# Booster_scheme_transformator.net
KiCad netlist of a schematic drawn in Altium Designer
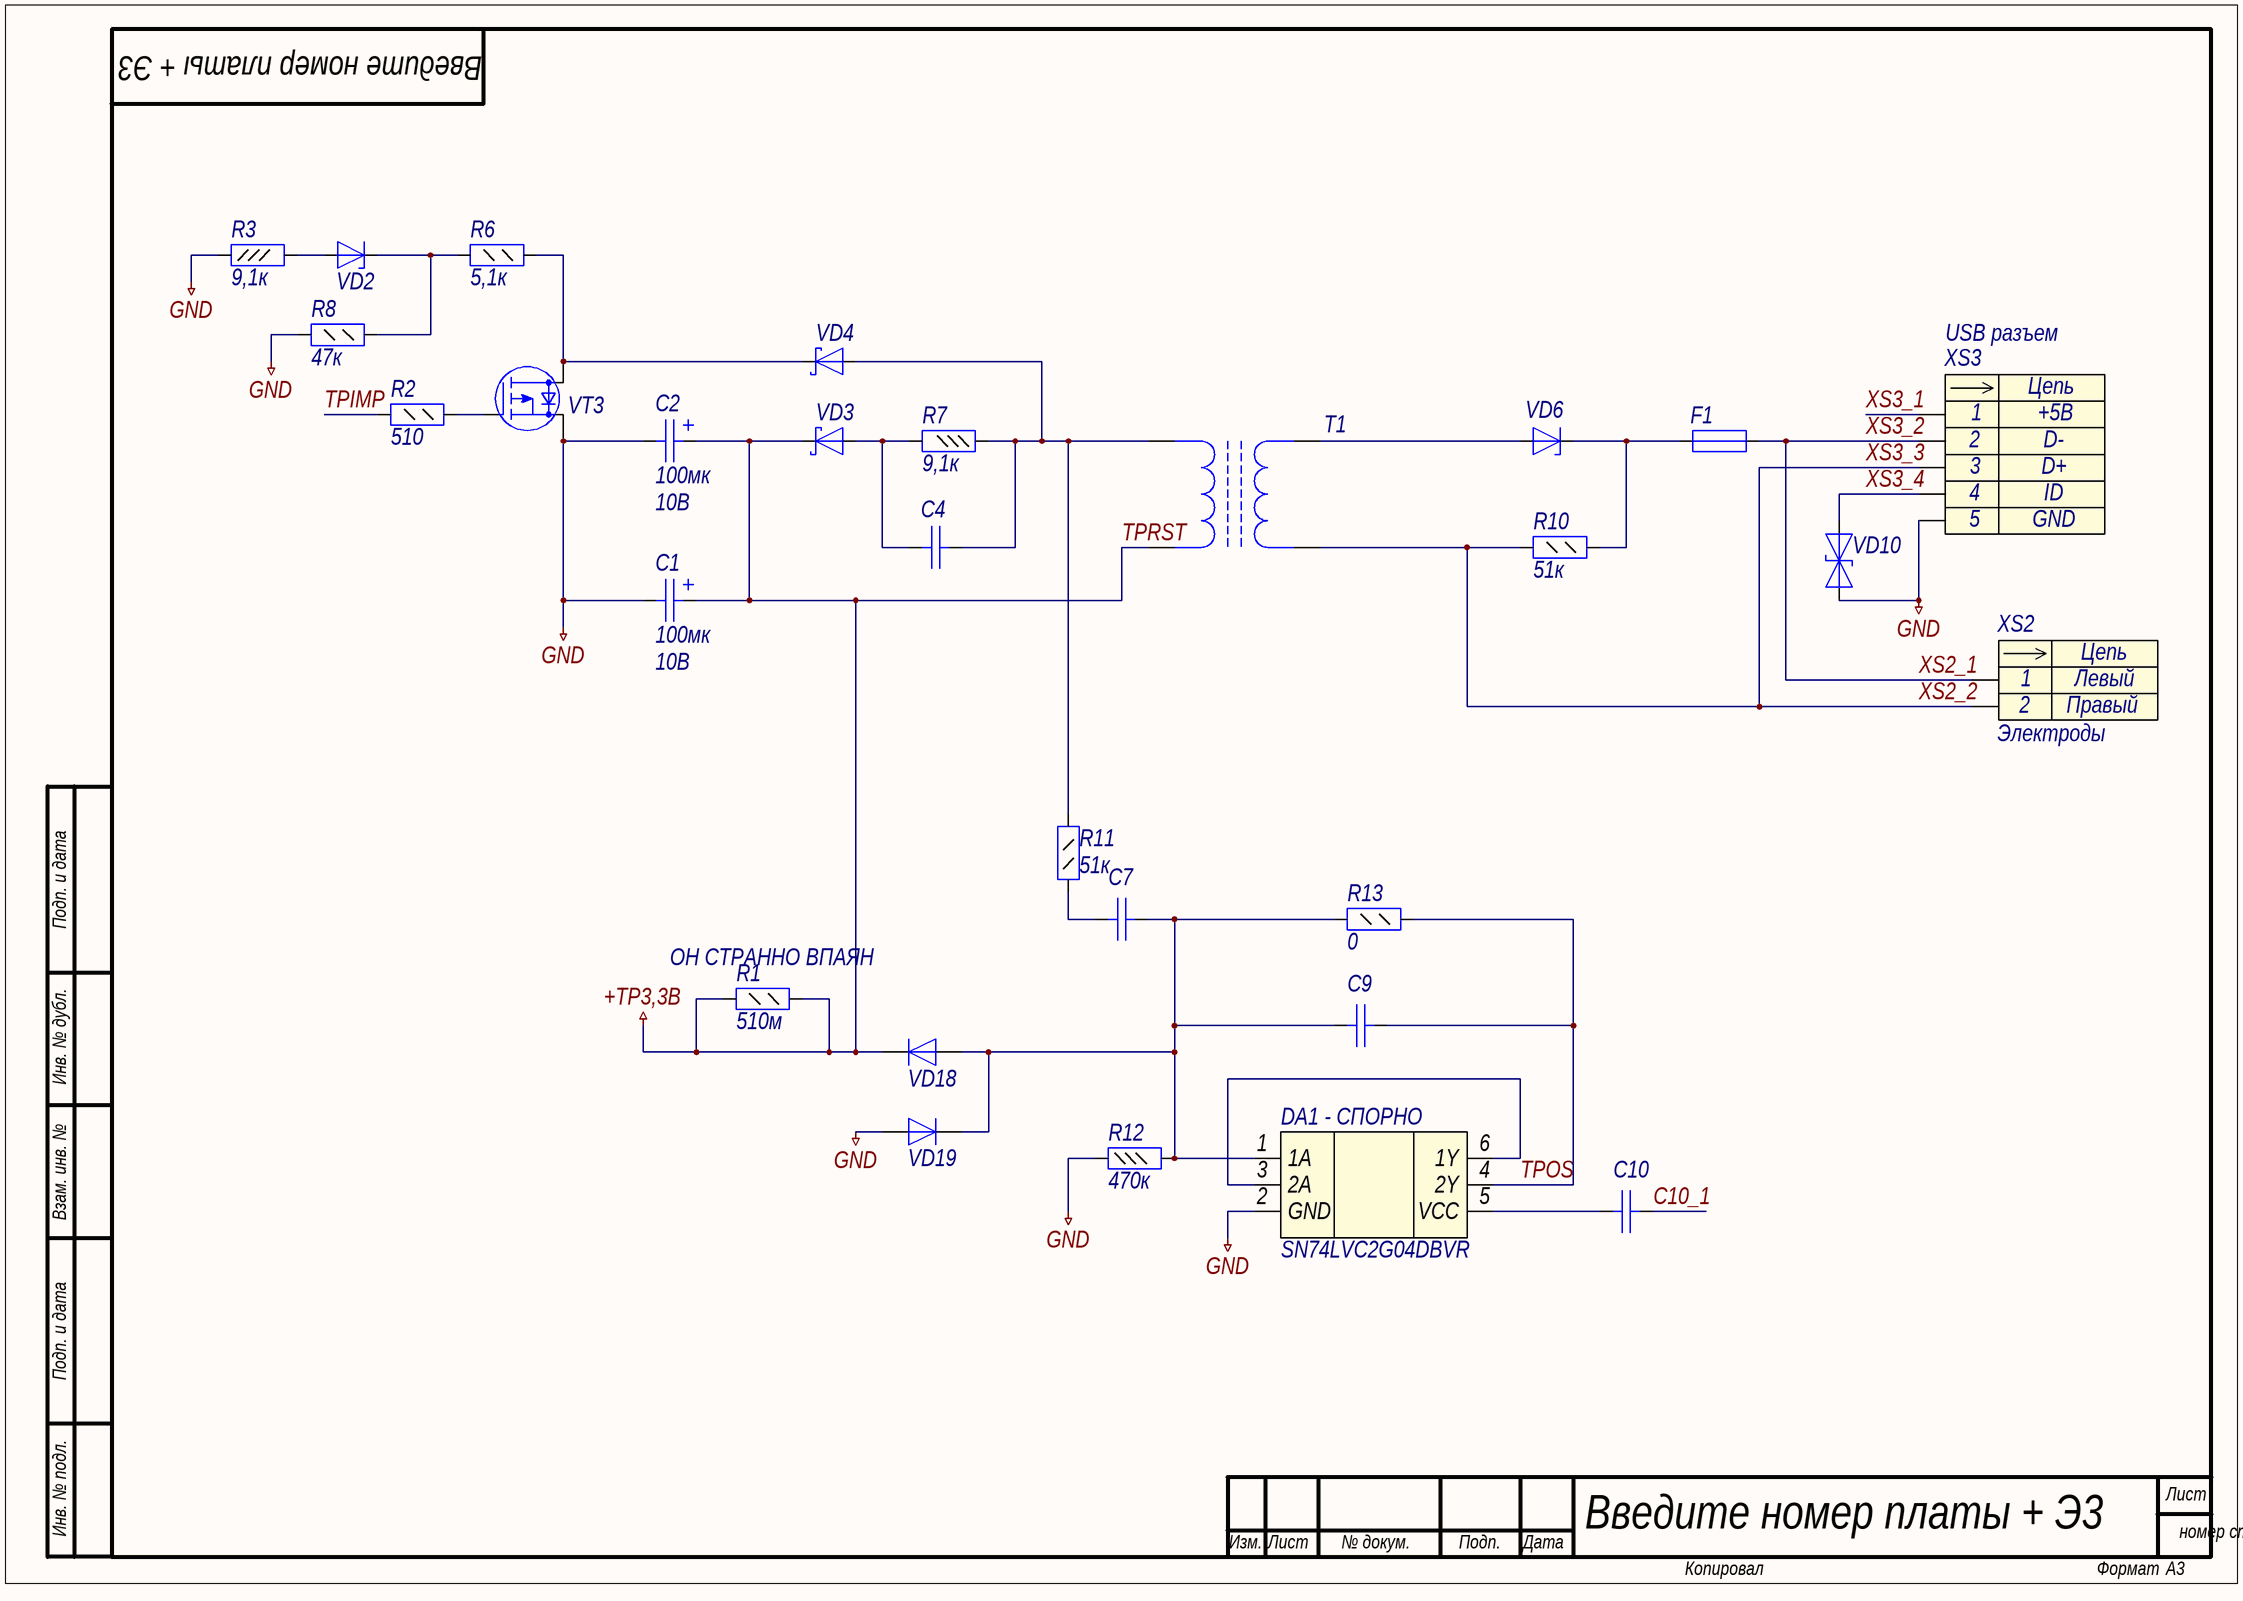
[diagram p0: Booster_scheme_transformator.SchDoc]

(export (version "E")
  (design (tool "Eeschema 10.0.6"))
  (components
    (comp (ref "C1")
      (value "100мк")
      (footprint "TANTAL CASE D")
      (description "Конденсатор полярный")
      (fields
        (field (name "VOLTAGE") "10В")
        (field (name "PART NUMBER") "T495D107K010ATA080")
        (field (name "Comment") "Capacitor_pol")
      )
      (libsource (lib "MOP44") (part "Capacitor_pol"))
    )
    (comp (ref "C2")
      (value "100мк")
      (footprint "TANTAL CASE D")
      (description "Конденсатор полярный")
      (fields
        (field (name "VOLTAGE") "10В")
        (field (name "PART NUMBER") "T495D107K010ATA080")
        (field (name "Comment") "Capacitor_pol")
      )
      (libsource (lib "MOP44") (part "Capacitor_pol"))
    )
    (comp (ref "C4")
      (value "Capacitor")
      (footprint "C0402")
      (description "Конденсатор")
      (fields (field (name "VOLTAGE") "50B") (field (name "PART NUMBER") "GRP1555C1HR47CZ01E"))
      (libsource (lib "MOP44") (part "Capacitor"))
    )
    (comp (ref "C7")
      (value "Capacitor")
      (footprint "C0402")
      (description "Конденсатор")
      (fields (field (name "VOLTAGE") "50B") (field (name "PART NUMBER") "GRP1555C1HR47CZ01E"))
      (libsource (lib "MOP44") (part "Capacitor"))
    )
    (comp (ref "C9")
      (value "Capacitor")
      (footprint "C0402")
      (description "Конденсатор")
      (fields (field (name "VOLTAGE") "50B") (field (name "PART NUMBER") "GRP1555C1HR47CZ01E"))
      (libsource (lib "MOP44") (part "Capacitor"))
    )
    (comp (ref "C10")
      (value "Capacitor")
      (footprint "C0402")
      (description "Конденсатор")
      (fields (field (name "VOLTAGE") "50B") (field (name "PART NUMBER") "GRP1555C1HR47CZ01E"))
      (libsource (lib "MOP44") (part "Capacitor"))
    )
    (comp (ref "DA1 - СПОРНО")
      (value "SN74LVC2G04DBVR")
      (footprint "SOT23-6")
      (description "Инвертирующий Триггер Шмитта")
      (fields (field (name "PART NUMBER") "SN74LVC2G04DBVR"))
      (libsource (lib "MOP44") (part "SN74LVC2G04DBVR"))
    )
    (comp (ref "F1")
      (value "Fuse")
      (footprint "FUSE812")
      (description "Предохранитель")
      (fields (field (name "PART NUMBER") "MF-MSMF050"))
      (libsource (lib "MOP44") (part "Fuse"))
    )
    (comp (ref "R1")
      (value "510м")
      (footprint "R0805")
      (description "Резистор")
      (fields (field (name "PART NUMBER") "RC0805FR-07510RL") (field (name "POWER") "0,125Вт"))
      (libsource (lib "MOP44") (part "Resistor_0,125Вт"))
    )
    (comp (ref "R2")
      (value "510")
      (footprint "R0805")
      (description "Резистор")
      (fields (field (name "PART NUMBER") "RC0805FR-07510RL") (field (name "POWER") "0,125Вт"))
      (libsource (lib "MOP44") (part "Resistor_0,125Вт"))
    )
    (comp (ref "R3")
      (value "9,1к")
      (footprint "R0603")
      (description "Резистор")
      (fields (field (name "PART NUMBER") "RC0603FR-079K1") (field (name "POWER") "0,062Вт"))
      (libsource (lib "MOP44") (part "Resistor_0,062Вт"))
    )
    (comp (ref "R6")
      (value "5,1к")
      (footprint "R0805")
      (description "Резистор")
      (fields (field (name "PART NUMBER") "RC0805FR-075K1") (field (name "POWER") "0,125Вт"))
      (libsource (lib "MOP44") (part "Resistor_0,125Вт"))
    )
    (comp (ref "R7")
      (value "9,1к")
      (footprint "R0603")
      (description "Резистор")
      (fields (field (name "PART NUMBER") "RC0603FR-079K1") (field (name "POWER") "0,062Вт"))
      (libsource (lib "") (part "Resistor_0,062Вт_1"))
    )
    (comp (ref "R8")
      (value "47к")
      (footprint "R0805")
      (description "Резистор")
      (fields (field (name "PART NUMBER") "RC0805FR-0747KL") (field (name "POWER") "0,125Вт"))
      (libsource (lib "MOP44") (part "Resistor_0,125Вт"))
    )
    (comp (ref "R10")
      (value "51к")
      (footprint "R0805")
      (description "Резистор")
      (fields (field (name "PART NUMBER") "RC0805FR-0751KL") (field (name "POWER") "0,125Вт"))
      (libsource (lib "MOP44") (part "Resistor_0,125Вт"))
    )
    (comp (ref "R11")
      (value "51к")
      (footprint "R0805")
      (description "Резистор")
      (fields (field (name "PART NUMBER") "RC0805FR-0751KL") (field (name "POWER") "0,125Вт"))
      (libsource (lib "") (part "Resistor_0,125Вт_1"))
    )
    (comp (ref "R12")
      (value "470к")
      (footprint "R0603")
      (description "Резистор")
      (fields (field (name "PART NUMBER") "RC0603FR-07470KL") (field (name "POWER") "0,062Вт"))
      (libsource (lib "") (part "Resistor_0,062Вт_2"))
    )
    (comp (ref "R13")
      (value "0")
      (footprint "R0805")
      (description "Резистор")
      (fields (field (name "PART NUMBER") "RC0805FR-070RL") (field (name "POWER") "0,125Вт"))
      (libsource (lib "MOP44") (part "Resistor_0,125Вт"))
    )
    (comp (ref "T1")
      (value "Transformer")
      (footprint "Transformer36mm")
      (description "EMI Suppression Filter")
      (libsource (lib "MOP44") (part "Transformer"))
    )
    (comp (ref "VD2")
      (value "DiodeZener")
      (footprint "SOT23-3")
      (description "Cтабилитрон (лавинный выпрямительный диод) односторонний")
      (fields (field (name "PART NUMBER") "BZX84-C30"))
      (libsource (lib "MOP44") (part "DiodeZener"))
    )
    (comp (ref "VD3")
      (value "DiodeSchottky")
      (footprint "SOD-123")
      (description "Диод Шоттки")
      (fields (field (name "PART NUMBER") "MBR0540"))
      (libsource (lib "MOP44") (part "DiodeSchottky"))
    )
    (comp (ref "VD4")
      (value "DiodeSchottky")
      (footprint "SOD-123")
      (description "Диод Шоттки")
      (fields (field (name "PART NUMBER") "MBR0540"))
      (libsource (lib "MOP44") (part "DiodeSchottky"))
    )
    (comp (ref "VD6")
      (value "DiodeZener")
      (footprint "SOT23-3")
      (description "Cтабилитрон (лавинный выпрямительный диод) односторонний")
      (fields (field (name "PART NUMBER") "BZX84-C5V1"))
      (libsource (lib "MOP44") (part "DiodeZener"))
    )
    (comp (ref "VD10")
      (value "DiodeZenerDual")
      (footprint "SMB")
      (description "Cтабилитрон (диод выпрямительный лавинный) двусторонний")
      (fields (field (name "PART NUMBER") "SMBJ8.5CA"))
      (libsource (lib "MOP44") (part "DiodeZenerDual"))
    )
    (comp (ref "VD18")
      (value "Diode")
      (footprint "SOD-123")
      (description "Диод")
      (fields (field (name "PART NUMBER") "MMSD4148"))
      (libsource (lib "MOP44") (part "Diode"))
    )
    (comp (ref "VD19")
      (value "Diode")
      (footprint "SOD-123")
      (description "Диод")
      (fields (field (name "PART NUMBER") "MMSD4148"))
      (libsource (lib "MOP44") (part "Diode"))
    )
    (comp (ref "VT3")
      (value "P-MOSFET")
      (footprint "SOT23-3")
      (description "N-MOSFET")
      (fields
        (field (name "PART NUMBER") "IRLML2244TRPbF")
        (field (name "MANUFACTURER") "International Rectifier")
      )
      (libsource (lib "MOP44") (part "P-MOSFET"))
    )
    (comp (ref "XS2")
      (value "Электроды")
      (footprint "CWF-2")
      (description "Разъем - 2 конт. вилка")
      (fields (field (name "PART NUMBER") "DS1069-2MVW6X"))
      (libsource (lib "MOP44") (part "Header_2_plg"))
    )
    (comp (ref "XS3")
      (value "USB разъем")
      (footprint "USB MINI AB RECEPTACLE")
      (description "USB Mini Type AB Receptacle")
      (fields (field (name "PART NUMBER") "UJ2-MABH-1-SMT-TR"))
      (libsource (lib "MOP44") (part "USB MINI RECEPTACLE"))
    )
  )
  (nets
    (net (code "1") (name "+TP3,3В") (class "Default")
      (node (ref "C1") (pin "1") (pinfunction "1_1") (pintype "passive"))
      (node (ref "C2") (pin "1") (pinfunction "1_1") (pintype "passive"))
      (node (ref "R1") (pin "1") (pinfunction "1_1") (pintype "passive"))
      (node (ref "R1") (pin "2") (pinfunction "2_2") (pintype "passive"))
      (node (ref "T1") (pin "2") (pinfunction "2_2") (pintype "passive"))
      (node (ref "VD18") (pin "1") (pinfunction "K_1") (pintype "passive"))
      (node (ref "VD3") (pin "1") (pinfunction "K_1") (pintype "passive"))
    )
    (net (code "2") (name "/C10_1") (class "Default")
      (node (ref "C10") (pin "1") (pinfunction "1_1") (pintype "passive"))
    )
    (net (code "3") (name "/TPIMP") (class "Default")
      (node (ref "R2") (pin "2") (pinfunction "2_2") (pintype "passive"))
    )
    (net (code "4") (name "/TPOS") (class "Default")
      (node (ref "C9") (pin "2") (pinfunction "2_2") (pintype "passive"))
      (node (ref "DA1 - СПОРНО") (pin "4") (pinfunction "2Y_4") (pintype "power_in"))
      (node (ref "R13") (pin "1") (pinfunction "1_1") (pintype "passive"))
    )
    (net (code "5") (name "/XS2_1") (class "Default")
      (node (ref "F1") (pin "1") (pinfunction "1_1") (pintype "passive"))
      (node (ref "XS2") (pin "1") (pinfunction "1_1") (pintype "passive"))
      (node (ref "XS3") (pin "2") (pinfunction "2_2") (pintype "passive"))
    )
    (net (code "6") (name "/XS2_2") (class "Default")
      (node (ref "R10") (pin "2") (pinfunction "2_2") (pintype "passive"))
      (node (ref "T1") (pin "4") (pinfunction "4_4") (pintype "passive"))
      (node (ref "XS2") (pin "2") (pinfunction "2_2") (pintype "passive"))
      (node (ref "XS3") (pin "3") (pinfunction "3_3") (pintype "passive"))
    )
    (net (code "7") (name "/XS3_1") (class "Default")
      (node (ref "XS3") (pin "1") (pinfunction "1_1") (pintype "passive"))
    )
    (net (code "8") (name "/XS3_4") (class "Default")
      (node (ref "VD10") (pin "2") (pinfunction "A_2") (pintype "passive"))
      (node (ref "XS3") (pin "4") (pinfunction "4_4") (pintype "passive"))
    )
    (net (code "9") (name "GND") (class "Default")
      (node (ref "C1") (pin "2") (pinfunction "2_2") (pintype "passive"))
      (node (ref "C2") (pin "2") (pinfunction "2_2") (pintype "passive"))
      (node (ref "DA1 - СПОРНО") (pin "2") (pinfunction "GND_2") (pintype "power_in"))
      (node (ref "R12") (pin "1") (pinfunction "1_1") (pintype "passive"))
      (node (ref "R3") (pin "1") (pinfunction "1_1") (pintype "passive"))
      (node (ref "R8") (pin "2") (pinfunction "2_2") (pintype "passive"))
      (node (ref "VD10") (pin "1") (pinfunction "K_1") (pintype "passive"))
      (node (ref "VD19") (pin "2") (pinfunction "A_2") (pintype "passive"))
      (node (ref "VT3") (pin "3") (pinfunction "S_3") (pintype "passive"))
      (node (ref "XS3") (pin "5") (pinfunction "5_5") (pintype "passive"))
    )
    (net (code "10") (name "Net-(C7-Pad2)") (class "Default")
      (node (ref "C7") (pin "2") (pinfunction "2_2") (pintype "passive"))
      (node (ref "R11") (pin "1") (pinfunction "1_1") (pintype "passive"))
    )
    (net (code "11") (name "Net-(DA1 - СПОРНО-1A)") (class "Default")
      (node (ref "C7") (pin "1") (pinfunction "1_1") (pintype "passive"))
      (node (ref "C9") (pin "1") (pinfunction "1_1") (pintype "passive"))
      (node (ref "DA1 - СПОРНО") (pin "1") (pinfunction "1A_1") (pintype "power_in"))
      (node (ref "R12") (pin "2") (pinfunction "2_2") (pintype "passive"))
      (node (ref "R13") (pin "2") (pinfunction "2_2") (pintype "passive"))
      (node (ref "VD18") (pin "2") (pinfunction "A_2") (pintype "passive"))
      (node (ref "VD19") (pin "1") (pinfunction "K_1") (pintype "passive"))
    )
    (net (code "12") (name "Net-(DA1 - СПОРНО-1Y)") (class "Default")
      (node (ref "DA1 - СПОРНО") (pin "3") (pinfunction "2A_3") (pintype "power_in"))
      (node (ref "DA1 - СПОРНО") (pin "6") (pinfunction "1Y_6") (pintype "power_in"))
    )
    (net (code "13") (name "Net-(DA1 - СПОРНО-VCC)") (class "Default")
      (node (ref "C10") (pin "2") (pinfunction "2_2") (pintype "passive"))
      (node (ref "DA1 - СПОРНО") (pin "5") (pinfunction "VCC_5") (pintype "power_in"))
    )
    (net (code "14") (name "Net-(VD2-A)") (class "Default")
      (node (ref "R3") (pin "2") (pinfunction "2_2") (pintype "passive"))
      (node (ref "VD2") (pin "2") (pinfunction "A_2") (pintype "passive"))
    )
    (net (code "15") (name "Net-(VD2-K)") (class "Default")
      (node (ref "R6") (pin "2") (pinfunction "2_2") (pintype "passive"))
      (node (ref "R8") (pin "1") (pinfunction "1_1") (pintype "passive"))
      (node (ref "VD2") (pin "1") (pinfunction "K_1") (pintype "passive"))
    )
    (net (code "16") (name "Net-(VD3-A)") (class "Default")
      (node (ref "C4") (pin "2") (pinfunction "2_2") (pintype "passive"))
      (node (ref "R7") (pin "2") (pinfunction "2_2") (pintype "passive"))
      (node (ref "VD3") (pin "2") (pinfunction "A_2") (pintype "passive"))
    )
    (net (code "17") (name "Net-(VD4-A)") (class "Default")
      (node (ref "C4") (pin "1") (pinfunction "1_1") (pintype "passive"))
      (node (ref "R11") (pin "2") (pinfunction "2_2") (pintype "passive"))
      (node (ref "R7") (pin "1") (pinfunction "1_1") (pintype "passive"))
      (node (ref "T1") (pin "1") (pinfunction "1_1") (pintype "passive"))
      (node (ref "VD4") (pin "2") (pinfunction "A_2") (pintype "passive"))
    )
    (net (code "18") (name "Net-(VD4-K)") (class "Default")
      (node (ref "R6") (pin "1") (pinfunction "1_1") (pintype "passive"))
      (node (ref "VD4") (pin "1") (pinfunction "K_1") (pintype "passive"))
      (node (ref "VT3") (pin "2") (pinfunction "D_2") (pintype "passive"))
    )
    (net (code "19") (name "Net-(VD6-A)") (class "Default")
      (node (ref "T1") (pin "3") (pinfunction "3_3") (pintype "passive"))
      (node (ref "VD6") (pin "2") (pinfunction "A_2") (pintype "passive"))
    )
    (net (code "20") (name "Net-(VD6-K)") (class "Default")
      (node (ref "F1") (pin "2") (pinfunction "2_2") (pintype "passive"))
      (node (ref "R10") (pin "1") (pinfunction "1_1") (pintype "passive"))
      (node (ref "VD6") (pin "1") (pinfunction "K_1") (pintype "passive"))
    )
    (net (code "21") (name "Net-(VT3-G)") (class "Default")
      (node (ref "R2") (pin "1") (pinfunction "1_1") (pintype "passive"))
      (node (ref "VT3") (pin "1") (pinfunction "G_1") (pintype "passive"))
    )
    (net (code "22") (name "unconnected-(T1-Pad1)") (class "Default")
      (node (ref "T1") (pin "1") (pinfunction "1_1") (pintype "passive"))
    )
    (net (code "23") (name "unconnected-(T1-Pad1)_1") (class "Default")
      (node (ref "T1") (pin "1") (pinfunction "1_1") (pintype "passive"))
    )
    (net (code "24") (name "unconnected-(T1-Pad2)") (class "Default")
      (node (ref "T1") (pin "2") (pinfunction "2_2") (pintype "passive"))
    )
    (net (code "25") (name "unconnected-(T1-Pad2)_1") (class "Default")
      (node (ref "T1") (pin "2") (pinfunction "2_2") (pintype "passive"))
    )
  )
)
